# BalEv_SD_card_v1_0.net
KiCad netlist of a schematic drawn in Altium Designer
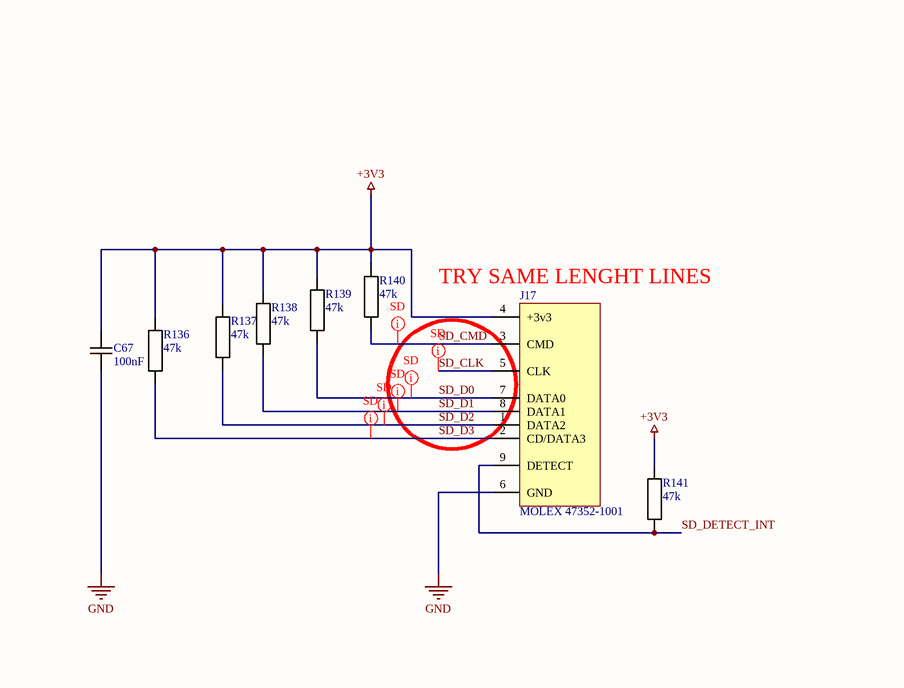
[diagram p0: BalEv_SD_card_v1_0.SchDoc]

(export (version "E")
  (design (tool "Eeschema 10.0.6"))
  (components
    (comp (ref "C67")
      (value "100nF")
      (footprint "CAPACITOR 1005 REFLOW")
      (description "Capacitor")
      (libsource (lib "Capacitor") (part "Capacitor"))
    )
    (comp (ref "J17")
      (value "MOLEX 47352-1001")
      (footprint "SD MICRO MOLEX 47352-1001")
      (description "SD Card  Micro 47352-1001")
      (libsource (lib "Connector") (part "SD-MICRO MOLEX 47352-1001"))
    )
    (comp (ref "R136")
      (value "47k")
      (footprint "RESISTOR 1005 REFLOW")
      (description "Resistor")
      (libsource (lib "Resistor") (part "Resistor"))
    )
    (comp (ref "R137")
      (value "47k")
      (footprint "RESISTOR 1005 REFLOW")
      (description "Resistor")
      (libsource (lib "Resistor") (part "Resistor"))
    )
    (comp (ref "R138")
      (value "47k")
      (footprint "RESISTOR 1005 REFLOW")
      (description "Resistor")
      (libsource (lib "Resistor") (part "Resistor"))
    )
    (comp (ref "R139")
      (value "47k")
      (footprint "RESISTOR 1005 REFLOW")
      (description "Resistor")
      (libsource (lib "Resistor") (part "Resistor"))
    )
    (comp (ref "R140")
      (value "47k")
      (footprint "RESISTOR 1005 REFLOW")
      (description "Resistor")
      (libsource (lib "Resistor") (part "Resistor"))
    )
    (comp (ref "R141")
      (value "47k")
      (footprint "RESISTOR 1005 REFLOW")
      (description "Resistor")
      (libsource (lib "Resistor") (part "Resistor"))
    )
  )
  (nets
    (net (code "1") (name "+3V3") (class "Default")
      (node (ref "C67") (pin "2") (pinfunction "2_2") (pintype "passive"))
      (node (ref "J17") (pin "4") (pinfunction "+3v3_4") (pintype "passive"))
      (node (ref "R136") (pin "2") (pinfunction "2_2") (pintype "passive"))
      (node (ref "R137") (pin "2") (pinfunction "2_2") (pintype "passive"))
      (node (ref "R138") (pin "2") (pinfunction "2_2") (pintype "passive"))
      (node (ref "R139") (pin "2") (pinfunction "2_2") (pintype "passive"))
      (node (ref "R140") (pin "2") (pinfunction "2_2") (pintype "passive"))
      (node (ref "R141") (pin "2") (pinfunction "2_2") (pintype "passive"))
    )
    (net (code "2") (name "/SD_CLK") (class "Default")
      (node (ref "J17") (pin "5") (pinfunction "CLK_5") (pintype "passive"))
    )
    (net (code "3") (name "/SD_CMD") (class "Default")
      (node (ref "J17") (pin "3") (pinfunction "CMD_3") (pintype "passive"))
      (node (ref "R140") (pin "1") (pinfunction "1_1") (pintype "passive"))
    )
    (net (code "4") (name "/SD_D0") (class "Default")
      (node (ref "J17") (pin "7") (pinfunction "DATA0_7") (pintype "passive"))
      (node (ref "R139") (pin "1") (pinfunction "1_1") (pintype "passive"))
    )
    (net (code "5") (name "/SD_D1") (class "Default")
      (node (ref "J17") (pin "8") (pinfunction "DATA1_8") (pintype "passive"))
      (node (ref "R138") (pin "1") (pinfunction "1_1") (pintype "passive"))
    )
    (net (code "6") (name "/SD_D2") (class "Default")
      (node (ref "J17") (pin "1") (pinfunction "DATA2_1") (pintype "passive"))
      (node (ref "R137") (pin "1") (pinfunction "1_1") (pintype "passive"))
    )
    (net (code "7") (name "/SD_D3") (class "Default")
      (node (ref "J17") (pin "2") (pinfunction "CD/DATA3_2") (pintype "passive"))
      (node (ref "R136") (pin "1") (pinfunction "1_1") (pintype "passive"))
    )
    (net (code "8") (name "/SD_DETECT_INT") (class "Default")
      (node (ref "J17") (pin "9") (pinfunction "DETECT_9") (pintype "passive"))
      (node (ref "R141") (pin "1") (pinfunction "1_1") (pintype "passive"))
    )
    (net (code "9") (name "GND") (class "Default")
      (node (ref "C67") (pin "1") (pinfunction "1_1") (pintype "passive"))
      (node (ref "J17") (pin "6") (pinfunction "GND_6") (pintype "passive"))
    )
  )
)
